# BlindAidRing.net
KiCad netlist of a schematic drawn in EAGLE
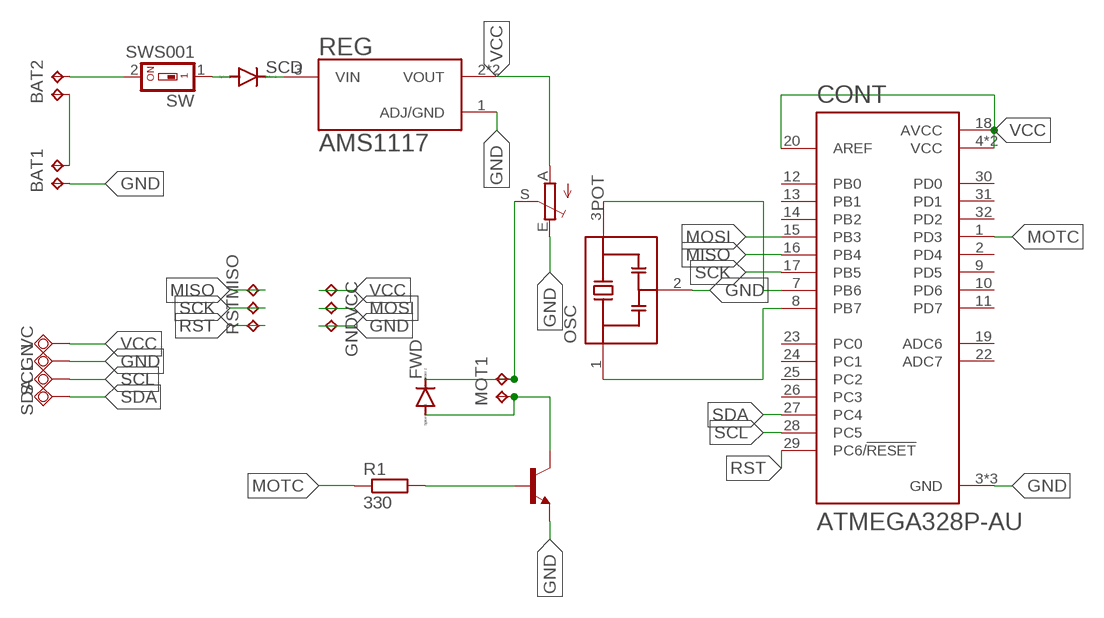
[diagram p0: schematic, sheet 1]

(export (version "E")
  (design (tool "Eeschema 10.0.6"))
  (components
    (comp (ref "BAT1")
      (value "TPTP20SQ")
      (footprint "eagle-import:TP20SQ")
      (libsource (lib "eagle-import") (part "TPTP20SQ"))
    )
    (comp (ref "BAT2")
      (value "TPTP20SQ")
      (footprint "eagle-import:TP20SQ")
      (libsource (lib "eagle-import") (part "TPTP20SQ"))
    )
    (comp (ref "BAT11")
      (value "TPTP20SQ")
      (footprint "eagle-import:TP20SQ")
      (libsource (lib "eagle-import") (part "TPTP20SQ"))
    )
    (comp (ref "BAT22")
      (value "TPTP20SQ")
      (footprint "eagle-import:TP20SQ")
      (libsource (lib "eagle-import") (part "TPTP20SQ"))
    )
    (comp (ref "CONT")
      (value "ATMEGA328P-AU")
      (footprint "eagle-import:QFP80P900X900X120-32N")
      (fields (field (name "MF") "Microchip Technology"))
      (libsource (lib "eagle-import") (part "ATMEGA328P-AU"))
    )
    (comp (ref "FWD")
      (value "CGRM4002-G")
      (footprint "eagle-import:SOD-123_MINI-SMA")
      (libsource (lib "eagle-import") (part "CGRM400-G2"))
    )
    (comp (ref "GN")
      (value "TPSQTP18SQ")
      (footprint "eagle-import:TP18SQ")
      (libsource (lib "eagle-import") (part "TPSQTP18SQ"))
    )
    (comp (ref "GND")
      (value "TPB1,27")
      (footprint "eagle-import:B1,27")
      (libsource (lib "eagle-import") (part "TPB1,27"))
    )
    (comp (ref "MISO")
      (value "TPB1,27")
      (footprint "eagle-import:B1,27")
      (libsource (lib "eagle-import") (part "TPB1,27"))
    )
    (comp (ref "MOSI")
      (value "TPB1,27")
      (footprint "eagle-import:B1,27")
      (libsource (lib "eagle-import") (part "TPB1,27"))
    )
    (comp (ref "MOT1")
      (value "TPTP20SQ")
      (footprint "eagle-import:TP20SQ")
      (libsource (lib "eagle-import") (part "TPTP20SQ"))
    )
    (comp (ref "MOT2")
      (value "TPTP20SQ")
      (footprint "eagle-import:TP20SQ")
      (libsource (lib "eagle-import") (part "TPTP20SQ"))
    )
    (comp (ref "OSC")
      (value "CSTCE16M0V53-R0")
      (footprint "eagle-import:OSC_CSTCE16M0V53-R0")
      (fields (field (name "MF") "Murata"))
      (libsource (lib "eagle-import") (part "CSTCE16M0V53-R0"))
    )
    (comp (ref "POT")
      (value "TRIM_EU-CA6V")
      (footprint "eagle-import:CA6V")
      (libsource (lib "eagle-import") (part "TRIM_EU-CA6V"))
    )
    (comp (ref "R1")
      (value "330")
      (footprint "eagle-import:R0603")
      (libsource (lib "eagle-import") (part "R-EU_R0603"))
    )
    (comp (ref "REG")
      (value "AMS1117")
      (footprint "eagle-import:SOT229P700X180-4N")
      (fields (field (name "MF") "Advanced Monolithic Systems"))
      (libsource (lib "eagle-import") (part "AMS1117"))
    )
    (comp (ref "RST")
      (value "TPB1,27")
      (footprint "eagle-import:B1,27")
      (libsource (lib "eagle-import") (part "TPB1,27"))
    )
    (comp (ref "SCD")
      (value "CGRM4002-G")
      (footprint "eagle-import:SOD-123_MINI-SMA")
      (libsource (lib "eagle-import") (part "CGRM400-G2"))
    )
    (comp (ref "SCK")
      (value "TPB1,27")
      (footprint "eagle-import:B1,27")
      (libsource (lib "eagle-import") (part "TPB1,27"))
    )
    (comp (ref "SCL")
      (value "TPSQTP18SQ")
      (footprint "eagle-import:TP18SQ")
      (libsource (lib "eagle-import") (part "TPSQTP18SQ"))
    )
    (comp (ref "SDA")
      (value "TPSQTP18SQ")
      (footprint "eagle-import:TP18SQ")
      (libsource (lib "eagle-import") (part "TPSQTP18SQ"))
    )
    (comp (ref "SW")
      (value "SWS001")
      (footprint "eagle-import:SMS-001")
      (libsource (lib "eagle-import") (part "SWS001"))
    )
    (comp (ref "T1")
      (value "-NPN-SOT23-EBC")
      (footprint "eagle-import:SOT23-EBC")
      (libsource (lib "eagle-import") (part "-NPN-SOT23-EBC"))
    )
    (comp (ref "VC")
      (value "TPSQTP18SQ")
      (footprint "eagle-import:TP18SQ")
      (libsource (lib "eagle-import") (part "TPSQTP18SQ"))
    )
    (comp (ref "VCC")
      (value "TPB1,27")
      (footprint "eagle-import:B1,27")
      (libsource (lib "eagle-import") (part "TPB1,27"))
    )
  )
  (nets
    (net (code "1") (name "GND") (class "Default")
      (node (ref "BAT1") (pin "TP") (pinfunction "TP_TP") (pintype "input"))
      (node (ref "CONT") (pin "21") (pinfunction "GND_21") (pintype "power_in"))
      (node (ref "CONT") (pin "3") (pinfunction "GND_3") (pintype "power_in"))
      (node (ref "CONT") (pin "5") (pinfunction "GND_5") (pintype "power_in"))
      (node (ref "GN") (pin "TP") (pinfunction "TP_TP") (pintype "input"))
      (node (ref "GND") (pin "TP") (pinfunction "TP_TP") (pintype "input"))
      (node (ref "OSC") (pin "2") (pinfunction "GND_2") (pintype "power_in"))
      (node (ref "POT") (pin "E") (pinfunction "E_E") (pintype "passive"))
      (node (ref "REG") (pin "1") (pinfunction "ADJ/GND_1") (pintype "power_in"))
      (node (ref "T1") (pin "E") (pinfunction "E_E") (pintype "passive"))
    )
    (net (code "2") (name "MISO") (class "Default")
      (node (ref "CONT") (pin "16") (pinfunction "PB4_16") (pintype "bidirectional"))
      (node (ref "MISO") (pin "TP") (pinfunction "TP_TP") (pintype "input"))
    )
    (net (code "3") (name "MOSI") (class "Default")
      (node (ref "CONT") (pin "15") (pinfunction "PB3_15") (pintype "bidirectional"))
      (node (ref "MOSI") (pin "TP") (pinfunction "TP_TP") (pintype "input"))
    )
    (net (code "4") (name "MOTC") (class "Default")
      (node (ref "CONT") (pin "1") (pinfunction "PD3_1") (pintype "bidirectional"))
      (node (ref "R1") (pin "1") (pinfunction "1_1") (pintype "passive"))
    )
    (net (code "5") (name "Net-(BAT11-PadTP)") (class "Default")
      (node (ref "BAT11") (pin "TP") (pinfunction "TP_TP") (pintype "input"))
      (node (ref "BAT2") (pin "TP") (pinfunction "TP_TP") (pintype "input"))
    )
    (net (code "6") (name "Net-(BAT22-PadTP)") (class "Default")
      (node (ref "BAT22") (pin "TP") (pinfunction "TP_TP") (pintype "input"))
      (node (ref "SW") (pin "2") (pinfunction "2_2") (pintype "passive"))
    )
    (net (code "7") (name "Net-(CONT-PB6)") (class "Default")
      (node (ref "CONT") (pin "7") (pinfunction "PB6_7") (pintype "bidirectional"))
      (node (ref "OSC") (pin "3") (pinfunction "OUT_3") (pintype "output"))
    )
    (net (code "8") (name "Net-(CONT-PB7)") (class "Default")
      (node (ref "CONT") (pin "8") (pinfunction "PB7_8") (pintype "bidirectional"))
      (node (ref "OSC") (pin "1") (pinfunction "IN_1") (pintype "input"))
    )
    (net (code "9") (name "Net-(FWD-PadA)") (class "Default")
      (node (ref "FWD") (pin "A") (pinfunction "A_A") (pintype "passive"))
      (node (ref "MOT1") (pin "TP") (pinfunction "TP_TP") (pintype "input"))
      (node (ref "T1") (pin "C") (pinfunction "C_C") (pintype "passive"))
    )
    (net (code "10") (name "Net-(FWD-PadC)") (class "Default")
      (node (ref "FWD") (pin "C") (pinfunction "C_C") (pintype "passive"))
      (node (ref "MOT2") (pin "TP") (pinfunction "TP_TP") (pintype "input"))
      (node (ref "POT") (pin "S") (pinfunction "S_S") (pintype "passive"))
    )
    (net (code "11") (name "Net-(R1-Pad2)") (class "Default")
      (node (ref "R1") (pin "2") (pinfunction "2_2") (pintype "passive"))
      (node (ref "T1") (pin "B") (pinfunction "B_B") (pintype "passive"))
    )
    (net (code "12") (name "Net-(REG-VIN)") (class "Default")
      (node (ref "REG") (pin "3") (pinfunction "VIN_3") (pintype "input"))
      (node (ref "SCD") (pin "C") (pinfunction "C_C") (pintype "passive"))
    )
    (net (code "13") (name "Net-(SCD-PadA)") (class "Default")
      (node (ref "SCD") (pin "A") (pinfunction "A_A") (pintype "passive"))
      (node (ref "SW") (pin "1") (pinfunction "1_1") (pintype "passive"))
    )
    (net (code "14") (name "RST") (class "Default")
      (node (ref "CONT") (pin "29") (pinfunction "PC6/~{RESET}_29") (pintype "bidirectional"))
      (node (ref "RST") (pin "TP") (pinfunction "TP_TP") (pintype "input"))
    )
    (net (code "15") (name "SCK") (class "Default")
      (node (ref "CONT") (pin "17") (pinfunction "PB5_17") (pintype "bidirectional"))
      (node (ref "SCK") (pin "TP") (pinfunction "TP_TP") (pintype "input"))
    )
    (net (code "16") (name "SCL") (class "Default")
      (node (ref "CONT") (pin "28") (pinfunction "PC5_28") (pintype "bidirectional"))
      (node (ref "SCL") (pin "TP") (pinfunction "TP_TP") (pintype "input"))
    )
    (net (code "17") (name "SDA") (class "Default")
      (node (ref "CONT") (pin "27") (pinfunction "PC4_27") (pintype "bidirectional"))
      (node (ref "SDA") (pin "TP") (pinfunction "TP_TP") (pintype "input"))
    )
    (net (code "18") (name "VCC") (class "Default")
      (node (ref "CONT") (pin "18") (pinfunction "AVCC_18") (pintype "power_in"))
      (node (ref "CONT") (pin "20") (pinfunction "AREF_20") (pintype "input"))
      (node (ref "CONT") (pin "4") (pinfunction "VCC_4") (pintype "power_in"))
      (node (ref "CONT") (pin "6") (pinfunction "VCC_6") (pintype "power_in"))
      (node (ref "POT") (pin "A") (pinfunction "A_A") (pintype "passive"))
      (node (ref "REG") (pin "2") (pinfunction "VOUT_2") (pintype "output"))
      (node (ref "REG") (pin "4") (pinfunction "VOUT_4") (pintype "output"))
      (node (ref "VC") (pin "TP") (pinfunction "TP_TP") (pintype "input"))
      (node (ref "VCC") (pin "TP") (pinfunction "TP_TP") (pintype "input"))
    )
    (net (code "19") (name "unconnected-(CONT-ADC6-Pad19)") (class "Default")
      (node (ref "CONT") (pin "19") (pinfunction "ADC6_19") (pintype "bidirectional"))
    )
    (net (code "20") (name "unconnected-(CONT-ADC7-Pad22)") (class "Default")
      (node (ref "CONT") (pin "22") (pinfunction "ADC7_22") (pintype "bidirectional"))
    )
    (net (code "21") (name "unconnected-(CONT-PB0-Pad12)") (class "Default")
      (node (ref "CONT") (pin "12") (pinfunction "PB0_12") (pintype "bidirectional"))
    )
    (net (code "22") (name "unconnected-(CONT-PB1-Pad13)") (class "Default")
      (node (ref "CONT") (pin "13") (pinfunction "PB1_13") (pintype "bidirectional"))
    )
    (net (code "23") (name "unconnected-(CONT-PB2-Pad14)") (class "Default")
      (node (ref "CONT") (pin "14") (pinfunction "PB2_14") (pintype "bidirectional"))
    )
    (net (code "24") (name "unconnected-(CONT-PC0-Pad23)") (class "Default")
      (node (ref "CONT") (pin "23") (pinfunction "PC0_23") (pintype "bidirectional"))
    )
    (net (code "25") (name "unconnected-(CONT-PC1-Pad24)") (class "Default")
      (node (ref "CONT") (pin "24") (pinfunction "PC1_24") (pintype "bidirectional"))
    )
    (net (code "26") (name "unconnected-(CONT-PC2-Pad25)") (class "Default")
      (node (ref "CONT") (pin "25") (pinfunction "PC2_25") (pintype "bidirectional"))
    )
    (net (code "27") (name "unconnected-(CONT-PC3-Pad26)") (class "Default")
      (node (ref "CONT") (pin "26") (pinfunction "PC3_26") (pintype "bidirectional"))
    )
    (net (code "28") (name "unconnected-(CONT-PD0-Pad30)") (class "Default")
      (node (ref "CONT") (pin "30") (pinfunction "PD0_30") (pintype "bidirectional"))
    )
    (net (code "29") (name "unconnected-(CONT-PD1-Pad31)") (class "Default")
      (node (ref "CONT") (pin "31") (pinfunction "PD1_31") (pintype "bidirectional"))
    )
    (net (code "30") (name "unconnected-(CONT-PD2-Pad32)") (class "Default")
      (node (ref "CONT") (pin "32") (pinfunction "PD2_32") (pintype "bidirectional"))
    )
    (net (code "31") (name "unconnected-(CONT-PD4-Pad2)") (class "Default")
      (node (ref "CONT") (pin "2") (pinfunction "PD4_2") (pintype "bidirectional"))
    )
    (net (code "32") (name "unconnected-(CONT-PD5-Pad9)") (class "Default")
      (node (ref "CONT") (pin "9") (pinfunction "PD5_9") (pintype "bidirectional"))
    )
    (net (code "33") (name "unconnected-(CONT-PD6-Pad10)") (class "Default")
      (node (ref "CONT") (pin "10") (pinfunction "PD6_10") (pintype "bidirectional"))
    )
    (net (code "34") (name "unconnected-(CONT-PD7-Pad11)") (class "Default")
      (node (ref "CONT") (pin "11") (pinfunction "PD7_11") (pintype "bidirectional"))
    )
  )
)
